# ANALOG_INPUT.net
KiCad netlist of a schematic drawn in Altium Designer
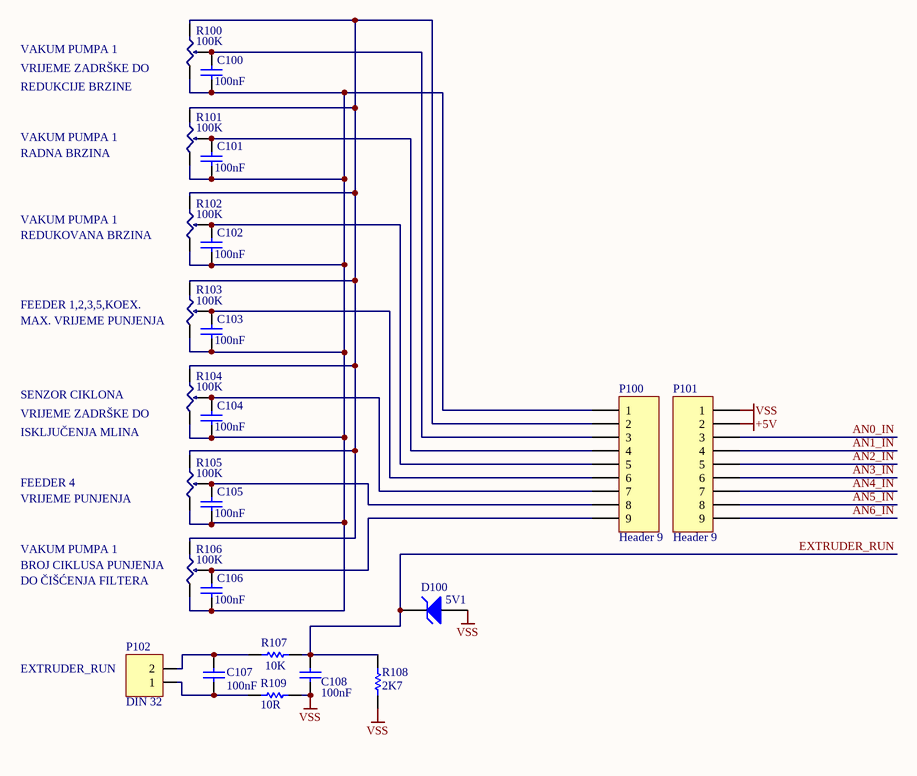
[diagram p0: ANALOG_INPUT.SchDoc]

(export (version "E")
  (design (tool "Eeschema 10.0.6"))
  (components
    (comp (ref "C100")
      (value "100nF")
      (footprint "1206")
      (description "Ceramic Chip Capacitor - Standard")
      (fields (field (name "PUBLISHER") "Altium Limited"))
      (libsource (lib "KEMET Chip Capacitor") (part "C1206"))
    )
    (comp (ref "C101")
      (value "100nF")
      (footprint "1206")
      (description "Ceramic Chip Capacitor - Standard")
      (fields (field (name "PUBLISHER") "Altium Limited"))
      (libsource (lib "KEMET Chip Capacitor") (part "C1206"))
    )
    (comp (ref "C102")
      (value "100nF")
      (footprint "1206")
      (description "Ceramic Chip Capacitor - Standard")
      (fields (field (name "PUBLISHER") "Altium Limited"))
      (libsource (lib "KEMET Chip Capacitor") (part "C1206"))
    )
    (comp (ref "C103")
      (value "100nF")
      (footprint "1206")
      (description "Ceramic Chip Capacitor - Standard")
      (fields (field (name "PUBLISHER") "Altium Limited"))
      (libsource (lib "KEMET Chip Capacitor") (part "C1206"))
    )
    (comp (ref "C104")
      (value "100nF")
      (footprint "1206")
      (description "Ceramic Chip Capacitor - Standard")
      (fields (field (name "PUBLISHER") "Altium Limited"))
      (libsource (lib "KEMET Chip Capacitor") (part "C1206"))
    )
    (comp (ref "C105")
      (value "100nF")
      (footprint "1206")
      (description "Ceramic Chip Capacitor - Standard")
      (fields (field (name "PUBLISHER") "Altium Limited"))
      (libsource (lib "KEMET Chip Capacitor") (part "C1206"))
    )
    (comp (ref "C106")
      (value "100nF")
      (footprint "1206")
      (description "Ceramic Chip Capacitor - Standard")
      (fields (field (name "PUBLISHER") "Altium Limited"))
      (libsource (lib "KEMET Chip Capacitor") (part "C1206"))
    )
    (comp (ref "C107")
      (value "100nF")
      (footprint "1206")
      (description "Ceramic Chip Capacitor - Standard")
      (fields (field (name "PUBLISHER") "Altium Limited"))
      (libsource (lib "KEMET Chip Capacitor") (part "C1206"))
    )
    (comp (ref "C108")
      (value "100nF")
      (footprint "1206")
      (description "Ceramic Chip Capacitor - Standard")
      (fields (field (name "PUBLISHER") "Altium Limited"))
      (libsource (lib "KEMET Chip Capacitor") (part "C1206"))
    )
    (comp (ref "D100")
      (value "5V1")
      (footprint "Philips Discrete Diode - Switching:SOD80C")
      (description "Zener Diode")
      (fields (field (name "PUBLISHER") "Altium Limited"))
      (libsource (lib "Miscellaneous Devices") (part "D Zener"))
    )
    (comp (ref "P100")
      (value "Header 9")
      (footprint "HDR1X9")
      (description "Header, 9-Pin")
      (fields (field (name "PUBLISHER") "Altium Limited"))
      (libsource (lib "Miscellaneous Connectors") (part "Header 9"))
    )
    (comp (ref "P101")
      (value "Header 9")
      (footprint "HDR1X9")
      (description "Header, 9-Pin")
      (fields (field (name "PUBLISHER") "Altium Limited"))
      (libsource (lib "") (part "Header 9_1"))
    )
    (comp (ref "P102")
      (value "DIN 32")
      (footprint "TERMINAL BLOK 2")
      (description "Terminal blok 2")
      (libsource (lib "TERMINAL_CONNECOR_2") (part "Terminal blok 2 pina"))
    )
    (comp (ref "R100") (value "100K") (footprint "Poti") (libsource (lib "PIHER POTI") (part "POTI")))
    (comp (ref "R101") (value "100K") (footprint "Poti") (libsource (lib "PIHER POTI") (part "POTI")))
    (comp (ref "R102") (value "100K") (footprint "Poti") (libsource (lib "PIHER POTI") (part "POTI")))
    (comp (ref "R103") (value "100K") (footprint "Poti") (libsource (lib "PIHER POTI") (part "POTI")))
    (comp (ref "R104") (value "100K") (footprint "Poti") (libsource (lib "PIHER POTI") (part "POTI")))
    (comp (ref "R105") (value "100K") (footprint "Poti") (libsource (lib "PIHER POTI") (part "POTI")))
    (comp (ref "R106") (value "100K") (footprint "Poti") (libsource (lib "PIHER POTI") (part "POTI")))
    (comp (ref "R107")
      (value "10K")
      (footprint "ERA-0805")
      (fields (field (name "PUBLISHER") "Altium Limited"))
      (libsource (lib "Panasonic Resistor") (part "ERA6Y"))
    )
    (comp (ref "R108")
      (value "2K7")
      (footprint "ERA-0805")
      (fields (field (name "PUBLISHER") "Altium Limited"))
      (libsource (lib "Panasonic Resistor") (part "ERA6Y"))
    )
    (comp (ref "R109")
      (value "10R")
      (footprint "ERA-0805")
      (fields (field (name "PUBLISHER") "Altium Limited"))
      (libsource (lib "Panasonic Resistor") (part "ERA6Y"))
    )
  )
  (nets
    (net (code "1") (name "+5V") (class "Default")
      (node (ref "P101") (pin "2") (pinfunction "2_2") (pintype "passive"))
    )
    (net (code "2") (name "/AN0_IN") (class "Default")
      (node (ref "P101") (pin "3") (pinfunction "3_3") (pintype "passive"))
    )
    (net (code "3") (name "/AN1_IN") (class "Default")
      (node (ref "P101") (pin "4") (pinfunction "4_4") (pintype "passive"))
    )
    (net (code "4") (name "/AN2_IN") (class "Default")
      (node (ref "P101") (pin "5") (pinfunction "5_5") (pintype "passive"))
    )
    (net (code "5") (name "/AN3_IN") (class "Default")
      (node (ref "P101") (pin "6") (pinfunction "6_6") (pintype "passive"))
    )
    (net (code "6") (name "/AN4_IN") (class "Default")
      (node (ref "P101") (pin "7") (pinfunction "7_7") (pintype "passive"))
    )
    (net (code "7") (name "/AN5_IN") (class "Default")
      (node (ref "P101") (pin "8") (pinfunction "8_8") (pintype "passive"))
    )
    (net (code "8") (name "/AN6_IN") (class "Default")
      (node (ref "P101") (pin "9") (pinfunction "9_9") (pintype "passive"))
    )
    (net (code "9") (name "/EXTRUDER_RUN") (class "Default")
      (node (ref "C108") (pin "1") (pinfunction "1_1") (pintype "passive"))
      (node (ref "D100") (pin "2") (pinfunction "K_2") (pintype "passive"))
      (node (ref "R107") (pin "1") (pinfunction "1_1") (pintype "passive"))
      (node (ref "R108") (pin "1") (pinfunction "1_1") (pintype "passive"))
    )
    (net (code "10") (name "Net-(C100-Pad1)") (class "Default")
      (node (ref "C100") (pin "1") (pinfunction "1_1") (pintype "passive"))
      (node (ref "C101") (pin "1") (pinfunction "1_1") (pintype "passive"))
      (node (ref "C102") (pin "1") (pinfunction "1_1") (pintype "passive"))
      (node (ref "C103") (pin "1") (pinfunction "1_1") (pintype "passive"))
      (node (ref "C104") (pin "1") (pinfunction "1_1") (pintype "passive"))
      (node (ref "C105") (pin "1") (pinfunction "1_1") (pintype "passive"))
      (node (ref "C106") (pin "1") (pinfunction "1_1") (pintype "passive"))
      (node (ref "P100") (pin "1") (pinfunction "1_1") (pintype "passive"))
      (node (ref "R100") (pin "2") (pinfunction "2_2") (pintype "passive"))
      (node (ref "R101") (pin "2") (pinfunction "2_2") (pintype "passive"))
      (node (ref "R102") (pin "2") (pinfunction "2_2") (pintype "passive"))
      (node (ref "R103") (pin "2") (pinfunction "2_2") (pintype "passive"))
      (node (ref "R104") (pin "2") (pinfunction "2_2") (pintype "passive"))
      (node (ref "R105") (pin "2") (pinfunction "2_2") (pintype "passive"))
      (node (ref "R106") (pin "2") (pinfunction "2_2") (pintype "passive"))
    )
    (net (code "11") (name "Net-(C100-Pad2)") (class "Default")
      (node (ref "C100") (pin "2") (pinfunction "2_2") (pintype "passive"))
      (node (ref "P100") (pin "3") (pinfunction "3_3") (pintype "passive"))
      (node (ref "R100") (pin "3") (pinfunction "3_3") (pintype "passive"))
    )
    (net (code "12") (name "Net-(C101-Pad2)") (class "Default")
      (node (ref "C101") (pin "2") (pinfunction "2_2") (pintype "passive"))
      (node (ref "P100") (pin "4") (pinfunction "4_4") (pintype "passive"))
      (node (ref "R101") (pin "3") (pinfunction "3_3") (pintype "passive"))
    )
    (net (code "13") (name "Net-(C102-Pad2)") (class "Default")
      (node (ref "C102") (pin "2") (pinfunction "2_2") (pintype "passive"))
      (node (ref "P100") (pin "5") (pinfunction "5_5") (pintype "passive"))
      (node (ref "R102") (pin "3") (pinfunction "3_3") (pintype "passive"))
    )
    (net (code "14") (name "Net-(C103-Pad2)") (class "Default")
      (node (ref "C103") (pin "2") (pinfunction "2_2") (pintype "passive"))
      (node (ref "P100") (pin "6") (pinfunction "6_6") (pintype "passive"))
      (node (ref "R103") (pin "3") (pinfunction "3_3") (pintype "passive"))
    )
    (net (code "15") (name "Net-(C104-Pad2)") (class "Default")
      (node (ref "C104") (pin "2") (pinfunction "2_2") (pintype "passive"))
      (node (ref "P100") (pin "7") (pinfunction "7_7") (pintype "passive"))
      (node (ref "R104") (pin "3") (pinfunction "3_3") (pintype "passive"))
    )
    (net (code "16") (name "Net-(C105-Pad2)") (class "Default")
      (node (ref "C105") (pin "2") (pinfunction "2_2") (pintype "passive"))
      (node (ref "P100") (pin "8") (pinfunction "8_8") (pintype "passive"))
      (node (ref "R105") (pin "3") (pinfunction "3_3") (pintype "passive"))
    )
    (net (code "17") (name "Net-(C106-Pad2)") (class "Default")
      (node (ref "C106") (pin "2") (pinfunction "2_2") (pintype "passive"))
      (node (ref "P100") (pin "9") (pinfunction "9_9") (pintype "passive"))
      (node (ref "R106") (pin "3") (pinfunction "3_3") (pintype "passive"))
    )
    (net (code "18") (name "Net-(C107-Pad1)") (class "Default")
      (node (ref "C107") (pin "1") (pinfunction "1_1") (pintype "passive"))
      (node (ref "P102") (pin "2") (pinfunction "2_2") (pintype "passive"))
      (node (ref "R107") (pin "2") (pinfunction "2_2") (pintype "passive"))
    )
    (net (code "19") (name "Net-(C107-Pad2)") (class "Default")
      (node (ref "C107") (pin "2") (pinfunction "2_2") (pintype "passive"))
      (node (ref "P102") (pin "1") (pinfunction "1_1") (pintype "passive"))
      (node (ref "R109") (pin "2") (pinfunction "2_2") (pintype "passive"))
    )
    (net (code "20") (name "Net-(P100-Pad2)") (class "Default")
      (node (ref "P100") (pin "2") (pinfunction "2_2") (pintype "passive"))
      (node (ref "R100") (pin "1") (pinfunction "1_1") (pintype "passive"))
      (node (ref "R101") (pin "1") (pinfunction "1_1") (pintype "passive"))
      (node (ref "R102") (pin "1") (pinfunction "1_1") (pintype "passive"))
      (node (ref "R103") (pin "1") (pinfunction "1_1") (pintype "passive"))
      (node (ref "R104") (pin "1") (pinfunction "1_1") (pintype "passive"))
      (node (ref "R105") (pin "1") (pinfunction "1_1") (pintype "passive"))
      (node (ref "R106") (pin "1") (pinfunction "1_1") (pintype "passive"))
    )
    (net (code "21") (name "VSS") (class "Default")
      (node (ref "C108") (pin "2") (pinfunction "2_2") (pintype "passive"))
      (node (ref "D100") (pin "1") (pinfunction "A_1") (pintype "passive"))
      (node (ref "P101") (pin "1") (pinfunction "1_1") (pintype "passive"))
      (node (ref "R108") (pin "2") (pinfunction "2_2") (pintype "passive"))
      (node (ref "R109") (pin "1") (pinfunction "1_1") (pintype "passive"))
    )
  )
)
